# DRV8462.net
KiCad netlist of a schematic drawn in Altium Designer
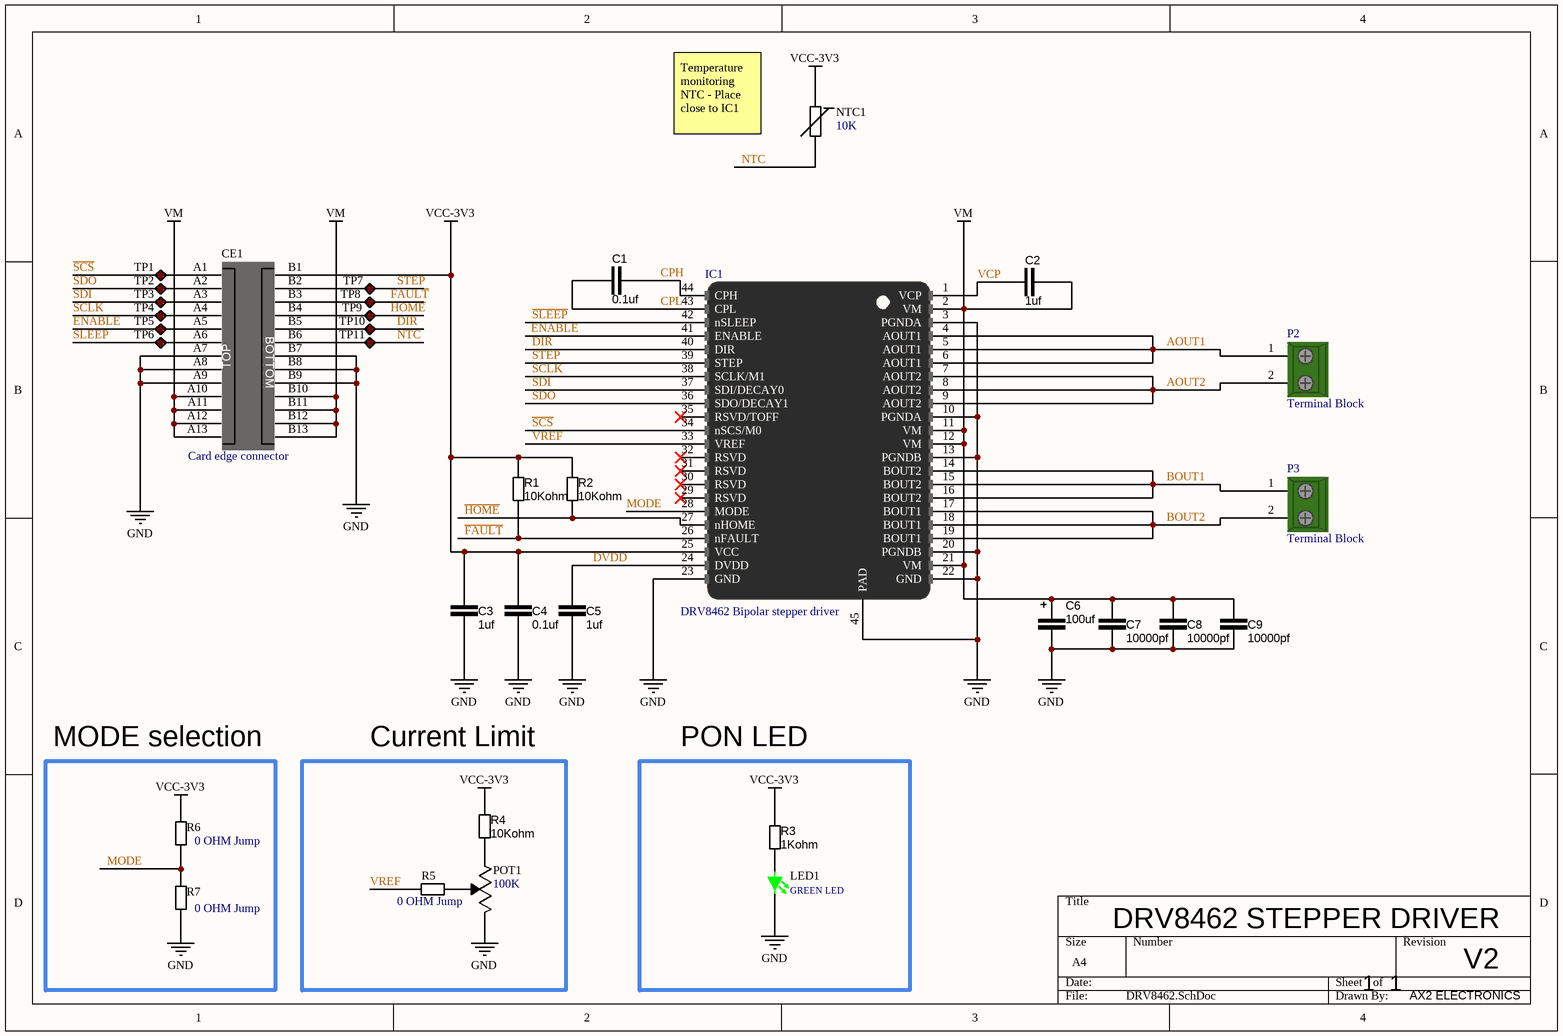
[diagram p0: DRV8462.SchDoc]

(export (version "E")
  (design (tool "Eeschema 10.0.6"))
  (components
    (comp (ref "C1")
      (value "0.1uf")
      (footprint "CAP_0603")
      (description "CAP CER 0.1uF 10V X7R 0603")
      (fields (field (name "DIGIKEY PART NUMBER") "732-7939-2-ND"))
      (libsource (lib "CapacitorsIntegrated") (part "0000012"))
    )
    (comp (ref "C2")
      (value "1uf")
      (footprint "CAP_0603")
      (description "CAP CER 1uF 0603 16V X7R")
      (fields (field (name "DIGIKEY PART NUMBER") "1276-1019-2-ND"))
      (libsource (lib "CapacitorsIntegrated") (part "0000009"))
    )
    (comp (ref "C3")
      (value "1uf")
      (footprint "CAP_0603")
      (description "CAP CER 1uF 10V X7R 0603")
      (fields (field (name "DIGIKEY PART NUMBER") "1276-1946-2-ND"))
      (libsource (lib "CapacitorsIntegrated") (part "0000011"))
    )
    (comp (ref "C4")
      (value "0.1uf")
      (footprint "CAP_0603")
      (description "CAP CER 0.1uF 10V X7R 0603")
      (fields (field (name "DIGIKEY PART NUMBER") "732-7939-2-ND"))
      (libsource (lib "") (part "0000012_1"))
    )
    (comp (ref "C5")
      (value "1uf")
      (footprint "CAP_0603")
      (description "CAP CER 1uF 0603 16V X7R")
      (fields (field (name "DIGIKEY PART NUMBER") "1276-1019-2-ND"))
      (libsource (lib "") (part "0000009_1"))
    )
    (comp (ref "C6")
      (value "100uf")
      (footprint "CAPAE7366X60M")
      (description "CAP ALUM POLY 100UF 20% 63V SMD")
      (fields (field (name "DIGIKEY PART NUMBER") "399-15648-2-ND"))
      (libsource (lib "CapacitorsIntegrated") (part "0000013"))
    )
    (comp (ref "C7")
      (value "10000pf")
      (footprint "CAP_0603")
      (description "CAP CER 10000PF 63V X7R 0603")
      (fields (field (name "DIGIKEY PART NUMBER") "1608-1294-2-ND"))
      (libsource (lib "CapacitorsIntegrated") (part "0000010"))
    )
    (comp (ref "C8")
      (value "10000pf")
      (footprint "CAP_0603")
      (description "CAP CER 10000PF 63V X7R 0603")
      (fields (field (name "DIGIKEY PART NUMBER") "1608-1294-2-ND"))
      (libsource (lib "CapacitorsIntegrated") (part "0000010"))
    )
    (comp (ref "C9")
      (value "10000pf")
      (footprint "CAP_0603")
      (description "CAP CER 10000PF 63V X7R 0603")
      (fields (field (name "DIGIKEY PART NUMBER") "1608-1294-2-ND"))
      (libsource (lib "CapacitorsIntegrated") (part "0000010"))
    )
    (comp (ref "CE1")
      (value "Card edge connector")
      (footprint "Edge Connector")
      (description "Card edge connector 26 PINs")
      (libsource (lib "ElectroMechanical") (part "00000007"))
    )
    (comp (ref "IC1")
      (value "DRV8462 Bipolar stepper driver")
      (footprint "TSOP64P810X120_HS-45N")
      (description "65-V, 10-A, DUAL H-BRIDGE STEPPER DRIVER")
      (fields
        (field (name "DIGIKEY PART NUMBER") "296-DRV8462DDWRTR-ND")
        (field (name "MOUSER PART NUMBER") "595-DRV8462DDWR")
      )
      (libsource (lib "IntegratedCircuits") (part "DRV8462"))
    )
    (comp (ref "LED1")
      (value "GREEN LED")
      (footprint "DIOC1608X04N")
      (description "LED GREEN DIFFUSED 0603 SMD")
      (libsource (lib "Miscellaneous_Lib1") (part "00000001"))
    )
    (comp (ref "NTC1")
      (value "10K")
      (footprint "SMD_0603")
      (description "THERMISTOR NTC 10KOHM 3380K 0603")
      (libsource (lib "Miscellaneous_Lib1") (part "00000003"))
    )
    (comp (ref "P2")
      (value "Terminal Block")
      (footprint "TERM_BLOCK 5mm 2PIN")
      (description "Terminal block 90 deg 5mm 2PIN")
      (fields (field (name "DIGIKEY PART NUMBER") "2057-EB20-02-C-ND"))
      (libsource (lib "ElectroMechanical") (part "00000001"))
    )
    (comp (ref "P3")
      (value "Terminal Block")
      (footprint "TERM_BLOCK 5mm 2PIN")
      (description "Terminal block 90 deg 5mm 2PIN")
      (fields (field (name "DIGIKEY PART NUMBER") "2057-EB20-02-C-ND"))
      (libsource (lib "ElectroMechanical") (part "00000001"))
    )
    (comp (ref "POT1")
      (value "100K")
      (footprint "TC33X-2_POT")
      (description "TRIMMER 100K OHM 0.1W J LEAD TOP")
      (libsource (lib "Miscellaneous_Lib1") (part "00000002"))
    )
    (comp (ref "R1")
      (value "10Kohm")
      (footprint "RES_0603")
      (description "RES 10K OHM 1% 1/10W 0603")
      (libsource (lib "ResistorsIntegrated") (part "R000001"))
    )
    (comp (ref "R2")
      (value "10Kohm")
      (footprint "RES_0603")
      (description "RES 10K OHM 1% 1/10W 0603")
      (libsource (lib "ResistorsIntegrated") (part "R000001"))
    )
    (comp (ref "R3")
      (value "1Kohm")
      (footprint "RES_0603")
      (description "RES 1K OHM 1% 1/10W 0603")
      (libsource (lib "ResistorsIntegrated") (part "R000004"))
    )
    (comp (ref "R4")
      (value "10Kohm")
      (footprint "RES_0603")
      (description "RES 10K OHM 1% 1/10W 0603")
      (libsource (lib "ResistorsIntegrated") (part "R000001"))
    )
    (comp (ref "R5")
      (value "0 OHM Jump")
      (footprint "RES_0603")
      (description "RES 0 OHM JUMPER 1/10W 0603")
      (libsource (lib "ResistorsIntegrated") (part "R000007"))
    )
    (comp (ref "R6")
      (value "0 OHM Jump")
      (footprint "RES_0603")
      (description "RES 0 OHM JUMPER 1/10W 0603")
      (libsource (lib "") (part "R000007_1"))
    )
    (comp (ref "R7")
      (value "0 OHM Jump")
      (footprint "RES_0603")
      (description "RES 0 OHM JUMPER 1/10W 0603")
      (libsource (lib "") (part "R000007_1"))
    )
    (comp (ref "TP1")
      (value "Test point")
      (footprint "TestPoint")
      (description "Test point 1mm")
      (libsource (lib "IntegratedCircuits") (part "TP002"))
    )
    (comp (ref "TP2")
      (value "Test point")
      (footprint "TestPoint")
      (description "Test point 1mm")
      (libsource (lib "IntegratedCircuits") (part "TP002"))
    )
    (comp (ref "TP3")
      (value "Test point")
      (footprint "TestPoint")
      (description "Test point 1mm")
      (libsource (lib "IntegratedCircuits") (part "TP002"))
    )
    (comp (ref "TP4")
      (value "Test point")
      (footprint "TestPoint")
      (description "Test point 1mm")
      (libsource (lib "IntegratedCircuits") (part "TP002"))
    )
    (comp (ref "TP5")
      (value "Test point")
      (footprint "TestPoint")
      (description "Test point 1mm")
      (libsource (lib "IntegratedCircuits") (part "TP002"))
    )
    (comp (ref "TP6")
      (value "Test point")
      (footprint "TestPoint")
      (description "Test point 1mm")
      (libsource (lib "IntegratedCircuits") (part "TP002"))
    )
    (comp (ref "TP7")
      (value "Test point")
      (footprint "TestPoint")
      (description "Test point 1mm")
      (libsource (lib "IntegratedCircuits") (part "TP002"))
    )
    (comp (ref "TP8")
      (value "Test point")
      (footprint "TestPoint")
      (description "Test point 1mm")
      (libsource (lib "IntegratedCircuits") (part "TP002"))
    )
    (comp (ref "TP9")
      (value "Test point")
      (footprint "TestPoint")
      (description "Test point 1mm")
      (libsource (lib "IntegratedCircuits") (part "TP002"))
    )
    (comp (ref "TP10")
      (value "Test point")
      (footprint "TestPoint")
      (description "Test point 1mm")
      (libsource (lib "IntegratedCircuits") (part "TP002"))
    )
    (comp (ref "TP11")
      (value "Test point")
      (footprint "TestPoint")
      (description "Test point 1mm")
      (libsource (lib "IntegratedCircuits") (part "TP002"))
    )
  )
  (nets
    (net (code "1") (name "/AOUT1") (class "Default")
      (node (ref "IC1") (pin "4") (pinfunction "AOUT1_4") (pintype "passive"))
      (node (ref "IC1") (pin "5") (pinfunction "AOUT1_5") (pintype "passive"))
      (node (ref "IC1") (pin "6") (pinfunction "AOUT1_6") (pintype "passive"))
      (node (ref "P2") (pin "1") (pinfunction "pin1_1") (pintype "passive"))
    )
    (net (code "2") (name "/AOUT2") (class "Default")
      (node (ref "IC1") (pin "7") (pinfunction "AOUT2_7") (pintype "passive"))
      (node (ref "IC1") (pin "8") (pinfunction "AOUT2_8") (pintype "passive"))
      (node (ref "IC1") (pin "9") (pinfunction "AOUT2_9") (pintype "passive"))
      (node (ref "P2") (pin "2") (pinfunction "pin2_2") (pintype "passive"))
    )
    (net (code "3") (name "/BOUT1") (class "Default")
      (node (ref "IC1") (pin "14") (pinfunction "BOUT2_14") (pintype "passive"))
      (node (ref "IC1") (pin "15") (pinfunction "BOUT2_15") (pintype "passive"))
      (node (ref "IC1") (pin "16") (pinfunction "BOUT2_16") (pintype "passive"))
      (node (ref "P3") (pin "1") (pinfunction "pin1_1") (pintype "passive"))
    )
    (net (code "4") (name "/BOUT2") (class "Default")
      (node (ref "IC1") (pin "17") (pinfunction "BOUT1_17") (pintype "passive"))
      (node (ref "IC1") (pin "18") (pinfunction "BOUT1_18") (pintype "passive"))
      (node (ref "IC1") (pin "19") (pinfunction "BOUT1_19") (pintype "passive"))
      (node (ref "P3") (pin "2") (pinfunction "pin2_2") (pintype "passive"))
    )
    (net (code "5") (name "/CPH") (class "Default")
      (node (ref "C1") (pin "2") (pinfunction "2_2") (pintype "passive"))
      (node (ref "IC1") (pin "44") (pinfunction "CPH_44") (pintype "passive"))
    )
    (net (code "6") (name "/CPL") (class "Default")
      (node (ref "C1") (pin "1") (pinfunction "1_1") (pintype "passive"))
      (node (ref "IC1") (pin "43") (pinfunction "CPL_43") (pintype "passive"))
    )
    (net (code "7") (name "/DIR") (class "Default")
      (node (ref "CE1") (pin "B5") (pinfunction "B5_B5") (pintype "passive"))
      (node (ref "IC1") (pin "40") (pinfunction "DIR_40") (pintype "passive"))
      (node (ref "TP10") (pin "1") (pinfunction "1_1") (pintype "passive"))
    )
    (net (code "8") (name "/DVDD") (class "Default")
      (node (ref "C5") (pin "2") (pinfunction "2_2") (pintype "passive"))
      (node (ref "IC1") (pin "24") (pinfunction "DVDD_24") (pintype "passive"))
    )
    (net (code "9") (name "/ENABLE") (class "Default")
      (node (ref "CE1") (pin "A5") (pinfunction "A5_A5") (pintype "passive"))
      (node (ref "IC1") (pin "41") (pinfunction "ENABLE_41") (pintype "passive"))
      (node (ref "TP5") (pin "1") (pinfunction "1_1") (pintype "passive"))
    )
    (net (code "10") (name "/MODE") (class "Default")
      (node (ref "IC1") (pin "28") (pinfunction "MODE_28") (pintype "passive"))
      (node (ref "R6") (pin "1") (pinfunction "1_1") (pintype "passive"))
      (node (ref "R7") (pin "2") (pinfunction "2_2") (pintype "passive"))
    )
    (net (code "11") (name "/NTC") (class "Default")
      (node (ref "CE1") (pin "B6") (pinfunction "B6_B6") (pintype "passive"))
      (node (ref "NTC1") (pin "1") (pinfunction "1_1") (pintype "passive"))
      (node (ref "TP11") (pin "1") (pinfunction "1_1") (pintype "passive"))
    )
    (net (code "12") (name "/SCLK") (class "Default")
      (node (ref "CE1") (pin "A4") (pinfunction "A4_A4") (pintype "passive"))
      (node (ref "IC1") (pin "38") (pinfunction "SCLK/M1_38") (pintype "passive"))
      (node (ref "TP4") (pin "1") (pinfunction "1_1") (pintype "passive"))
    )
    (net (code "13") (name "/SDI") (class "Default")
      (node (ref "CE1") (pin "A3") (pinfunction "A3_A3") (pintype "passive"))
      (node (ref "IC1") (pin "37") (pinfunction "SDI/DECAY0_37") (pintype "passive"))
      (node (ref "TP3") (pin "1") (pinfunction "1_1") (pintype "passive"))
    )
    (net (code "14") (name "/SDO") (class "Default")
      (node (ref "CE1") (pin "A2") (pinfunction "A2_A2") (pintype "passive"))
      (node (ref "IC1") (pin "36") (pinfunction "SDO/DECAY1_36") (pintype "passive"))
      (node (ref "TP2") (pin "1") (pinfunction "1_1") (pintype "passive"))
    )
    (net (code "15") (name "/STEP") (class "Default")
      (node (ref "CE1") (pin "B2") (pinfunction "B2_B2") (pintype "passive"))
      (node (ref "IC1") (pin "39") (pinfunction "STEP_39") (pintype "passive"))
      (node (ref "TP7") (pin "1") (pinfunction "1_1") (pintype "passive"))
    )
    (net (code "16") (name "/VCP") (class "Default")
      (node (ref "C2") (pin "1") (pinfunction "1_1") (pintype "passive"))
      (node (ref "IC1") (pin "1") (pinfunction "VCP_1") (pintype "passive"))
    )
    (net (code "17") (name "/VREF") (class "Default")
      (node (ref "IC1") (pin "33") (pinfunction "VREF_33") (pintype "passive"))
      (node (ref "R5") (pin "1") (pinfunction "1_1") (pintype "passive"))
    )
    (net (code "18") (name "/~{FAULT}") (class "Default")
      (node (ref "CE1") (pin "B3") (pinfunction "B3_B3") (pintype "passive"))
      (node (ref "IC1") (pin "26") (pinfunction "nFAULT_26") (pintype "passive"))
      (node (ref "R1") (pin "1") (pinfunction "1_1") (pintype "passive"))
      (node (ref "TP8") (pin "1") (pinfunction "1_1") (pintype "passive"))
    )
    (net (code "19") (name "/~{HOME}") (class "Default")
      (node (ref "CE1") (pin "B4") (pinfunction "B4_B4") (pintype "passive"))
      (node (ref "IC1") (pin "27") (pinfunction "nHOME_27") (pintype "passive"))
      (node (ref "R2") (pin "1") (pinfunction "1_1") (pintype "passive"))
      (node (ref "TP9") (pin "1") (pinfunction "1_1") (pintype "passive"))
    )
    (net (code "20") (name "/~{SCS}") (class "Default")
      (node (ref "CE1") (pin "A1") (pinfunction "A1_A1") (pintype "passive"))
      (node (ref "IC1") (pin "34") (pinfunction "nSCS/M0_34") (pintype "passive"))
      (node (ref "TP1") (pin "1") (pinfunction "1_1") (pintype "passive"))
    )
    (net (code "21") (name "/~{SLEEP}") (class "Default")
      (node (ref "CE1") (pin "A6") (pinfunction "A6_A6") (pintype "passive"))
      (node (ref "IC1") (pin "42") (pinfunction "nSLEEP_42") (pintype "passive"))
      (node (ref "TP6") (pin "1") (pinfunction "1_1") (pintype "passive"))
    )
    (net (code "22") (name "GND") (class "Default")
      (node (ref "C3") (pin "2") (pinfunction "2_2") (pintype "passive"))
      (node (ref "C4") (pin "1") (pinfunction "1_1") (pintype "passive"))
      (node (ref "C5") (pin "1") (pinfunction "1_1") (pintype "passive"))
      (node (ref "C6") (pin "1") (pinfunction "1_1") (pintype "passive"))
      (node (ref "C7") (pin "1") (pinfunction "1_1") (pintype "passive"))
      (node (ref "C8") (pin "1") (pinfunction "1_1") (pintype "passive"))
      (node (ref "C9") (pin "1") (pinfunction "1_1") (pintype "passive"))
      (node (ref "CE1") (pin "A7") (pinfunction "A7_A7") (pintype "passive"))
      (node (ref "CE1") (pin "A8") (pinfunction "A8_A8") (pintype "passive"))
      (node (ref "CE1") (pin "A9") (pinfunction "A9_A9") (pintype "passive"))
      (node (ref "CE1") (pin "B7") (pinfunction "B7_B7") (pintype "passive"))
      (node (ref "CE1") (pin "B8") (pinfunction "B8_B8") (pintype "passive"))
      (node (ref "CE1") (pin "B9") (pinfunction "B9_B9") (pintype "passive"))
      (node (ref "IC1") (pin "10") (pinfunction "PGNDA_10") (pintype "passive"))
      (node (ref "IC1") (pin "13") (pinfunction "PGNDB_13") (pintype "passive"))
      (node (ref "IC1") (pin "20") (pinfunction "PGNDB_20") (pintype "passive"))
      (node (ref "IC1") (pin "22") (pinfunction "GND_22") (pintype "passive"))
      (node (ref "IC1") (pin "23") (pinfunction "GND_23") (pintype "passive"))
      (node (ref "IC1") (pin "3") (pinfunction "PGNDA_3") (pintype "passive"))
      (node (ref "IC1") (pin "45") (pinfunction "PAD_45") (pintype "passive"))
      (node (ref "LED1") (pin "2") (pinfunction "2_2") (pintype "passive"))
      (node (ref "POT1") (pin "3") (pinfunction "3_3") (pintype "passive"))
      (node (ref "R7") (pin "1") (pinfunction "1_1") (pintype "passive"))
    )
    (net (code "23") (name "Net-(LED1-Pad1)") (class "Default")
      (node (ref "LED1") (pin "1") (pinfunction "1_1") (pintype "passive"))
      (node (ref "R3") (pin "1") (pinfunction "1_1") (pintype "passive"))
    )
    (net (code "24") (name "Net-(POT1-Pad1)") (class "Default")
      (node (ref "POT1") (pin "1") (pinfunction "1_1") (pintype "passive"))
      (node (ref "R4") (pin "1") (pinfunction "1_1") (pintype "passive"))
    )
    (net (code "25") (name "Net-(POT1-Pad2)") (class "Default")
      (node (ref "POT1") (pin "2") (pinfunction "2_2") (pintype "passive"))
      (node (ref "R5") (pin "2") (pinfunction "2_2") (pintype "passive"))
    )
    (net (code "26") (name "VCC-3V3") (class "Default")
      (node (ref "C3") (pin "1") (pinfunction "1_1") (pintype "passive"))
      (node (ref "C4") (pin "2") (pinfunction "2_2") (pintype "passive"))
      (node (ref "CE1") (pin "B1") (pinfunction "B1_B1") (pintype "passive"))
      (node (ref "IC1") (pin "25") (pinfunction "VCC_25") (pintype "passive"))
      (node (ref "NTC1") (pin "2") (pinfunction "2_2") (pintype "passive"))
      (node (ref "R1") (pin "2") (pinfunction "2_2") (pintype "passive"))
      (node (ref "R2") (pin "2") (pinfunction "2_2") (pintype "passive"))
      (node (ref "R3") (pin "2") (pinfunction "2_2") (pintype "passive"))
      (node (ref "R4") (pin "2") (pinfunction "2_2") (pintype "passive"))
      (node (ref "R6") (pin "2") (pinfunction "2_2") (pintype "passive"))
    )
    (net (code "27") (name "VM") (class "Default")
      (node (ref "C2") (pin "2") (pinfunction "2_2") (pintype "passive"))
      (node (ref "C6") (pin "2") (pinfunction "2_2") (pintype "passive"))
      (node (ref "C7") (pin "2") (pinfunction "2_2") (pintype "passive"))
      (node (ref "C8") (pin "2") (pinfunction "2_2") (pintype "passive"))
      (node (ref "C9") (pin "2") (pinfunction "2_2") (pintype "passive"))
      (node (ref "CE1") (pin "A10") (pinfunction "A10_A10") (pintype "passive"))
      (node (ref "CE1") (pin "A11") (pinfunction "A11_A11") (pintype "passive"))
      (node (ref "CE1") (pin "A12") (pinfunction "A12_A12") (pintype "passive"))
      (node (ref "CE1") (pin "A13") (pinfunction "A13_A13") (pintype "passive"))
      (node (ref "CE1") (pin "B10") (pinfunction "B10_B10") (pintype "passive"))
      (node (ref "CE1") (pin "B11") (pinfunction "B11_B11") (pintype "passive"))
      (node (ref "CE1") (pin "B12") (pinfunction "B12_B12") (pintype "passive"))
      (node (ref "CE1") (pin "B13") (pinfunction "B13_B13") (pintype "passive"))
      (node (ref "IC1") (pin "11") (pinfunction "VM_11") (pintype "passive"))
      (node (ref "IC1") (pin "12") (pinfunction "VM_12") (pintype "passive"))
      (node (ref "IC1") (pin "2") (pinfunction "VM_2") (pintype "passive"))
      (node (ref "IC1") (pin "21") (pinfunction "VM_21") (pintype "passive"))
    )
    (net (code "28") (name "unconnected-(IC1-RSVD-Pad29)") (class "Default")
      (node (ref "IC1") (pin "29") (pinfunction "RSVD_29") (pintype "passive+no_connect"))
    )
    (net (code "29") (name "unconnected-(IC1-RSVD-Pad30)") (class "Default")
      (node (ref "IC1") (pin "30") (pinfunction "RSVD_30") (pintype "passive+no_connect"))
    )
    (net (code "30") (name "unconnected-(IC1-RSVD-Pad31)") (class "Default")
      (node (ref "IC1") (pin "31") (pinfunction "RSVD_31") (pintype "passive+no_connect"))
    )
    (net (code "31") (name "unconnected-(IC1-RSVD-Pad32)") (class "Default")
      (node (ref "IC1") (pin "32") (pinfunction "RSVD_32") (pintype "passive+no_connect"))
    )
    (net (code "32") (name "unconnected-(IC1-RSVD{slash}TOFF-Pad35)") (class "Default")
      (node (ref "IC1") (pin "35") (pinfunction "RSVD/TOFF_35") (pintype "passive+no_connect"))
    )
  )
)
